# Simple_LED-driver_on_BP2857d.net
KiCad netlist of a schematic drawn in Altium Designer
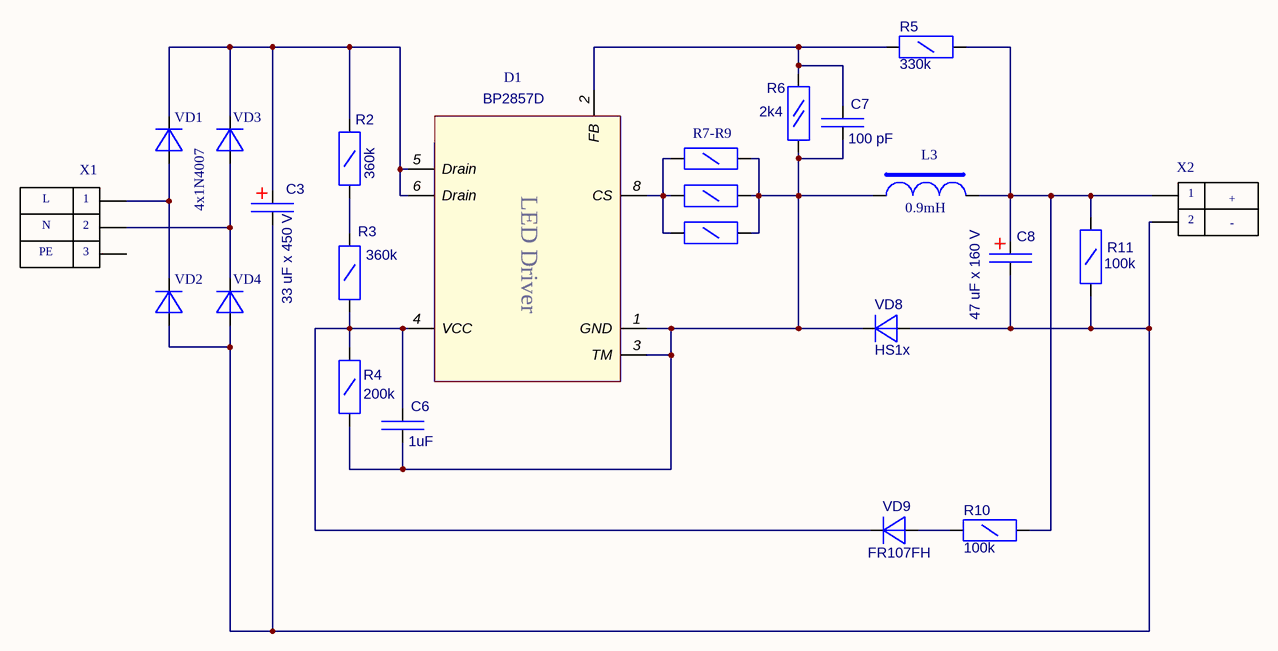
[diagram p0: Simple LED-driver on BP2857d.SchDoc]

(export (version "E")
  (design (tool "Eeschema 10.0.6"))
  (components
    (comp (ref "C3")
      (value "33 uF x 450 V")
      (footprint "CAPR E 12.5x20, pitch 5mm; hor.")
      (description "Cap Pol GOST")
      (fields (field (name "TOLERANCE") "10%") (field (name "Comment") "Cap Pol"))
      (libsource (lib "General Devices (laz)") (part "Cap Pol"))
    )
    (comp (ref "C6")
      (value "1uF")
      (footprint "CAPC2012 (0805)")
      (description "Ceramic")
      (fields (field (name "VOLTAGE") "25V") (field (name "Comment") "Cap_SMD"))
      (libsource (lib "General Devices (laz)") (part "Cap_SMD"))
    )
    (comp (ref "C7")
      (value "100 pF")
      (footprint "CAPC2012 (0805)")
      (description "Ceramic")
      (fields (field (name "VOLTAGE") "25V") (field (name "Comment") "Cap_SMD"))
      (libsource (lib "General Devices (laz)") (part "Cap_SMD"))
    )
    (comp (ref "C8")
      (value "47 uF x 160 V")
      (footprint "CAPR E 10x12.5 pitch 5 - hor")
      (description "Cap Pol GOST")
      (fields (field (name "TOLERANCE") "10%") (field (name "Comment") "Cap Pol"))
      (libsource (lib "General Devices (laz)") (part "Cap Pol"))
    )
    (comp (ref "D1")
      (value "BP2857D")
      (description "IC LED Driver Buck")
      (fields (field (name "Comment") "BP2857D (DIP7)"))
      (libsource (lib "General Devices (laz)") (part "BP2857D (DIP7)"))
    )
    (comp (ref "L3")
      (value "LED-E16-0.9mH-0.5g-H")
      (footprint "VRI-E16-8-G")
      (description "LED.E16-30mH-0.5g.H")
      (fields (field (name "VALUE2") "0.9mH"))
      (libsource (lib "General Devices (laz)") (part "Choke LED E16"))
    )
    (comp (ref "R2")
      (value "360k")
      (footprint "RESC3216(1206)N")
      (description "Resistor GOST")
      (fields (field (name "TOLERANCE") "5%") (field (name "VOLTAGE") "200Vdc"))
      (libsource (lib "") (part "Res 1/4W_1"))
    )
    (comp (ref "R3")
      (value "360k")
      (footprint "RESC3216(1206)N")
      (description "Resistor GOST")
      (fields (field (name "TOLERANCE") "5%") (field (name "VOLTAGE") "200Vdc"))
      (libsource (lib "") (part "Res 1/4W_1"))
    )
    (comp (ref "R4")
      (value "200k")
      (footprint "RESC3216(1206)N")
      (description "Resistor GOST")
      (fields (field (name "TOLERANCE") "5%") (field (name "VOLTAGE") "200Vdc"))
      (libsource (lib "") (part "Res 1/4W_1"))
    )
    (comp (ref "R5")
      (value "330k")
      (footprint "RESC3216(1206)N")
      (description "Resistor GOST")
      (fields (field (name "TOLERANCE") "5%") (field (name "VOLTAGE") "200Vdc"))
      (libsource (lib "General Devices (laz)") (part "Res 1/4W"))
    )
    (comp (ref "R6")
      (value "2k4")
      (footprint "RESC2012(0805)")
      (description "Resistor GOST")
      (fields (field (name "TOLERANCE") "5%") (field (name "Comment") "Res 1/8W"))
      (libsource (lib "General Devices (laz)") (part "Res 1/8W"))
    )
    (comp (ref "R7")
      (value "Res 1/4W")
      (footprint "RESC3216(1206)N")
      (description "Resistor GOST")
      (fields
        (field (name "TOLERANCE") "5%")
        (field (name "VOLTAGE") "200Vdc")
        (field (name "DESIGNATOR2") "R7-R9")
      )
      (libsource (lib "General Devices (laz)") (part "Res 1/4W"))
    )
    (comp (ref "R8")
      (value "Res 1/4W")
      (footprint "RESC3216(1206)N")
      (description "Resistor GOST")
      (fields (field (name "TOLERANCE") "5%") (field (name "VOLTAGE") "200Vdc"))
      (libsource (lib "General Devices (laz)") (part "Res 1/4W"))
    )
    (comp (ref "R9")
      (value "Res 1/4W")
      (footprint "RESC3216(1206)N")
      (description "Resistor GOST")
      (fields (field (name "TOLERANCE") "5%") (field (name "VOLTAGE") "200Vdc"))
      (libsource (lib "General Devices (laz)") (part "Res 1/4W"))
    )
    (comp (ref "R10")
      (value "100k")
      (footprint "RESC3216(1206)N")
      (description "Resistor GOST")
      (fields (field (name "TOLERANCE") "5%") (field (name "VOLTAGE") "200Vdc"))
      (libsource (lib "General Devices (laz)") (part "Res 1/4W"))
    )
    (comp (ref "R11")
      (value "100k")
      (footprint "RESC3216(1206)N")
      (description "Resistor GOST")
      (fields (field (name "TOLERANCE") "5%") (field (name "VOLTAGE") "200Vdc"))
      (libsource (lib "") (part "Res 1/4W_1"))
    )
    (comp (ref "VD1")
      (value "~")
      (footprint "CD4532-1812 (mod)")
      (description "Diode GOST")
      (fields (field (name "VALUE2") "4x1N4007"))
      (libsource (lib "General Devices (laz)") (part "Diode1"))
    )
    (comp (ref "VD2")
      (value "~")
      (footprint "CD4532-1812 (mod)")
      (description "Diode GOST")
      (libsource (lib "General Devices (laz)") (part "Diode1"))
    )
    (comp (ref "VD3")
      (value "Diode HS1x")
      (footprint "CD4532-1812 (mod)")
      (description "Diode GOST")
      (libsource (lib "General Devices (laz)") (part "Diode1"))
    )
    (comp (ref "VD4")
      (value "~")
      (footprint "CD4532-1812 (mod)")
      (description "Diode GOST")
      (libsource (lib "General Devices (laz)") (part "Diode1"))
    )
    (comp (ref "VD8")
      (value "HS1x")
      (footprint "CD4532-1812 (mod)")
      (description "Diode HS1x (GOST)")
      (fields (field (name "Comment") "Diode HS1x"))
      (libsource (lib "General Devices (laz)") (part "Diode HS1x"))
    )
    (comp (ref "VD9")
      (value "FR107FH")
      (description "Diode HS1x (GOST)")
      (fields (field (name "MANUFACTURER") "KEXIN") (field (name "Comment") "Diode HS1x"))
      (libsource (lib "General Devices (laz)") (part "Diode HS1x"))
    )
    (comp (ref "X1")
      (value "Connector_3_pin")
      (footprint "ZIP-Ballast3")
      (libsource (lib "GOST") (part "Connector_3_pin"))
    )
    (comp (ref "X2")
      (value "Connector_output_2pin_nobody")
      (footprint "ZIP-Ballast2")
      (libsource (lib "GOST") (part "Connector_output_2pin_nobody"))
    )
  )
  (nets
    (net (code "1") (name "Net-(C3-Pad1)") (class "Default")
      (node (ref "C3") (pin "1") (pinfunction "1_1") (pintype "passive"))
      (node (ref "D1") (pin "5") (pinfunction "Drain_5") (pintype "passive"))
      (node (ref "D1") (pin "6") (pinfunction "Drain_6") (pintype "passive"))
      (node (ref "R2") (pin "2") (pinfunction "2_2") (pintype "passive"))
      (node (ref "VD1") (pin "2") (pinfunction "2_2") (pintype "passive"))
      (node (ref "VD3") (pin "2") (pinfunction "2_2") (pintype "passive"))
    )
    (net (code "2") (name "Net-(C3-Pad2)") (class "Default")
      (node (ref "C3") (pin "2") (pinfunction "2_2") (pintype "passive"))
      (node (ref "C8") (pin "2") (pinfunction "2_2") (pintype "passive"))
      (node (ref "R11") (pin "1") (pinfunction "1_1") (pintype "passive"))
      (node (ref "VD2") (pin "1") (pinfunction "1_1") (pintype "passive"))
      (node (ref "VD4") (pin "1") (pinfunction "1_1") (pintype "passive"))
      (node (ref "VD8") (pin "1") (pinfunction "1_1") (pintype "passive"))
      (node (ref "X2") (pin "2") (pinfunction "2_2") (pintype "passive"))
    )
    (net (code "3") (name "Net-(D1-CS)") (class "Default")
      (node (ref "D1") (pin "8") (pinfunction "CS_8") (pintype "passive"))
      (node (ref "R7") (pin "2") (pinfunction "2_2") (pintype "passive"))
      (node (ref "R8") (pin "2") (pinfunction "2_2") (pintype "passive"))
      (node (ref "R9") (pin "2") (pinfunction "2_2") (pintype "passive"))
    )
    (net (code "4") (name "Net-(D1-FB)") (class "Default")
      (node (ref "C7") (pin "1") (pinfunction "1_1") (pintype "passive"))
      (node (ref "D1") (pin "2") (pinfunction "FB_2") (pintype "passive"))
      (node (ref "R5") (pin "2") (pinfunction "2_2") (pintype "passive"))
      (node (ref "R6") (pin "1") (pinfunction "1_1") (pintype "passive"))
    )
    (net (code "5") (name "Net-(D1-GND)") (class "Default")
      (node (ref "C6") (pin "2") (pinfunction "2_2") (pintype "passive"))
      (node (ref "C7") (pin "2") (pinfunction "2_2") (pintype "passive"))
      (node (ref "D1") (pin "1") (pinfunction "GND_1") (pintype "passive"))
      (node (ref "D1") (pin "3") (pinfunction "TM_3") (pintype "passive"))
      (node (ref "L3") (pin "14") (pinfunction "Pri+_14") (pintype "passive"))
      (node (ref "R4") (pin "1") (pinfunction "1_1") (pintype "passive"))
      (node (ref "R6") (pin "2") (pinfunction "2_2") (pintype "passive"))
      (node (ref "R7") (pin "1") (pinfunction "1_1") (pintype "passive"))
      (node (ref "R8") (pin "1") (pinfunction "1_1") (pintype "passive"))
      (node (ref "R9") (pin "1") (pinfunction "1_1") (pintype "passive"))
      (node (ref "VD8") (pin "2") (pinfunction "2_2") (pintype "passive"))
    )
    (net (code "6") (name "Net-(D1-VCC)") (class "Default")
      (node (ref "C6") (pin "1") (pinfunction "1_1") (pintype "passive"))
      (node (ref "D1") (pin "4") (pinfunction "VCC_4") (pintype "passive"))
      (node (ref "R3") (pin "1") (pinfunction "1_1") (pintype "passive"))
      (node (ref "R4") (pin "2") (pinfunction "2_2") (pintype "passive"))
      (node (ref "VD9") (pin "2") (pinfunction "2_2") (pintype "passive"))
    )
    (net (code "7") (name "Net-(L3-Pri-)") (class "Default")
      (node (ref "C8") (pin "1") (pinfunction "1_1") (pintype "passive"))
      (node (ref "L3") (pin "1") (pinfunction "Pri-_1") (pintype "passive"))
      (node (ref "R10") (pin "1") (pinfunction "1_1") (pintype "passive"))
      (node (ref "R11") (pin "2") (pinfunction "2_2") (pintype "passive"))
      (node (ref "R5") (pin "1") (pinfunction "1_1") (pintype "passive"))
      (node (ref "X2") (pin "1") (pinfunction "1_1") (pintype "passive"))
    )
    (net (code "8") (name "Net-(R2-Pad1)") (class "Default")
      (node (ref "R2") (pin "1") (pinfunction "1_1") (pintype "passive"))
      (node (ref "R3") (pin "2") (pinfunction "2_2") (pintype "passive"))
    )
    (net (code "9") (name "Net-(R10-Pad2)") (class "Default")
      (node (ref "R10") (pin "2") (pinfunction "2_2") (pintype "passive"))
      (node (ref "VD9") (pin "1") (pinfunction "1_1") (pintype "passive"))
    )
    (net (code "10") (name "Net-(VD1-Pad1)") (class "Default")
      (node (ref "VD1") (pin "1") (pinfunction "1_1") (pintype "passive"))
      (node (ref "VD2") (pin "2") (pinfunction "2_2") (pintype "passive"))
      (node (ref "X1") (pin "1") (pinfunction "1_1") (pintype "passive"))
    )
    (net (code "11") (name "Net-(VD3-Pad1)") (class "Default")
      (node (ref "VD3") (pin "1") (pinfunction "1_1") (pintype "passive"))
      (node (ref "VD4") (pin "2") (pinfunction "2_2") (pintype "passive"))
      (node (ref "X1") (pin "2") (pinfunction "2_2") (pintype "passive"))
    )
    (net (code "12") (name "unconnected-(X1-Pad3)") (class "Default")
      (node (ref "X1") (pin "3") (pinfunction "3_3") (pintype "passive"))
    )
  )
)
